# Snippet_of_Audio_Jack_buttom.net
KiCad netlist of a schematic drawn in Altium Designer
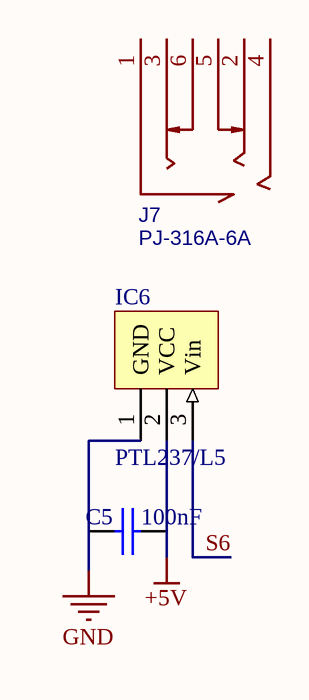
[diagram p0: Snippet of Audio_Jack_buttom.SchDoc]

(export (version "E")
  (design (tool "Eeschema 10.0.6"))
  (components
    (comp (ref "C5")
      (value "100nF")
      (footprint "C_0603")
      (description "贴片电容")
      (libsource (lib "IntLib-Passive") (part "Cap_Chip"))
    )
    (comp (ref "IC6")
      (value "PTL237/L5")
      (footprint "PLT237/L5")
      (description "光纤发射模组")
      (libsource (lib "Connector-Audio") (part "Audio_PTL237/L5"))
    )
    (comp (ref "J7")
      (value "PJ-316A-6A")
      (footprint "PJ-316A-6A")
      (description "3.5音频链接座子")
      (fields (field (name "BOM_SUPPLIER PART") "C128987"))
      (libsource (lib "IntLib-Connector") (part "Audio_PJ-316A-6A"))
    )
  )
  (nets
    (net (code "1") (name "+5V") (class "Default")
      (node (ref "C5") (pin "2") (pinfunction "2_2") (pintype "passive"))
      (node (ref "IC6") (pin "2") (pinfunction "VCC_2") (pintype "power_in"))
    )
    (net (code "2") (name "/S6") (class "Default")
      (node (ref "IC6") (pin "3") (pinfunction "Vin_3") (pintype "input"))
    )
    (net (code "3") (name "GND") (class "Default")
      (node (ref "C5") (pin "1") (pinfunction "1_1") (pintype "passive"))
      (node (ref "IC6") (pin "1") (pinfunction "GND_1") (pintype "power_in"))
    )
    (net (code "4") (name "unconnected-(J7-Pad1)") (class "Default")
      (node (ref "J7") (pin "1") (pinfunction "1_1") (pintype "passive"))
    )
    (net (code "5") (name "unconnected-(J7-Pad2)") (class "Default")
      (node (ref "J7") (pin "2") (pinfunction "2_2") (pintype "passive"))
    )
    (net (code "6") (name "unconnected-(J7-Pad3)") (class "Default")
      (node (ref "J7") (pin "3") (pinfunction "3_3") (pintype "passive"))
    )
    (net (code "7") (name "unconnected-(J7-Pad4)") (class "Default")
      (node (ref "J7") (pin "4") (pinfunction "4_4") (pintype "passive"))
    )
    (net (code "8") (name "unconnected-(J7-Pad5)") (class "Default")
      (node (ref "J7") (pin "5") (pinfunction "5_5") (pintype "passive"))
    )
    (net (code "9") (name "unconnected-(J7-Pad6)") (class "Default")
      (node (ref "J7") (pin "6") (pinfunction "6_6") (pintype "passive"))
    )
  )
)
